# od-aws.net
KiCad netlist of a schematic drawn in EAGLE
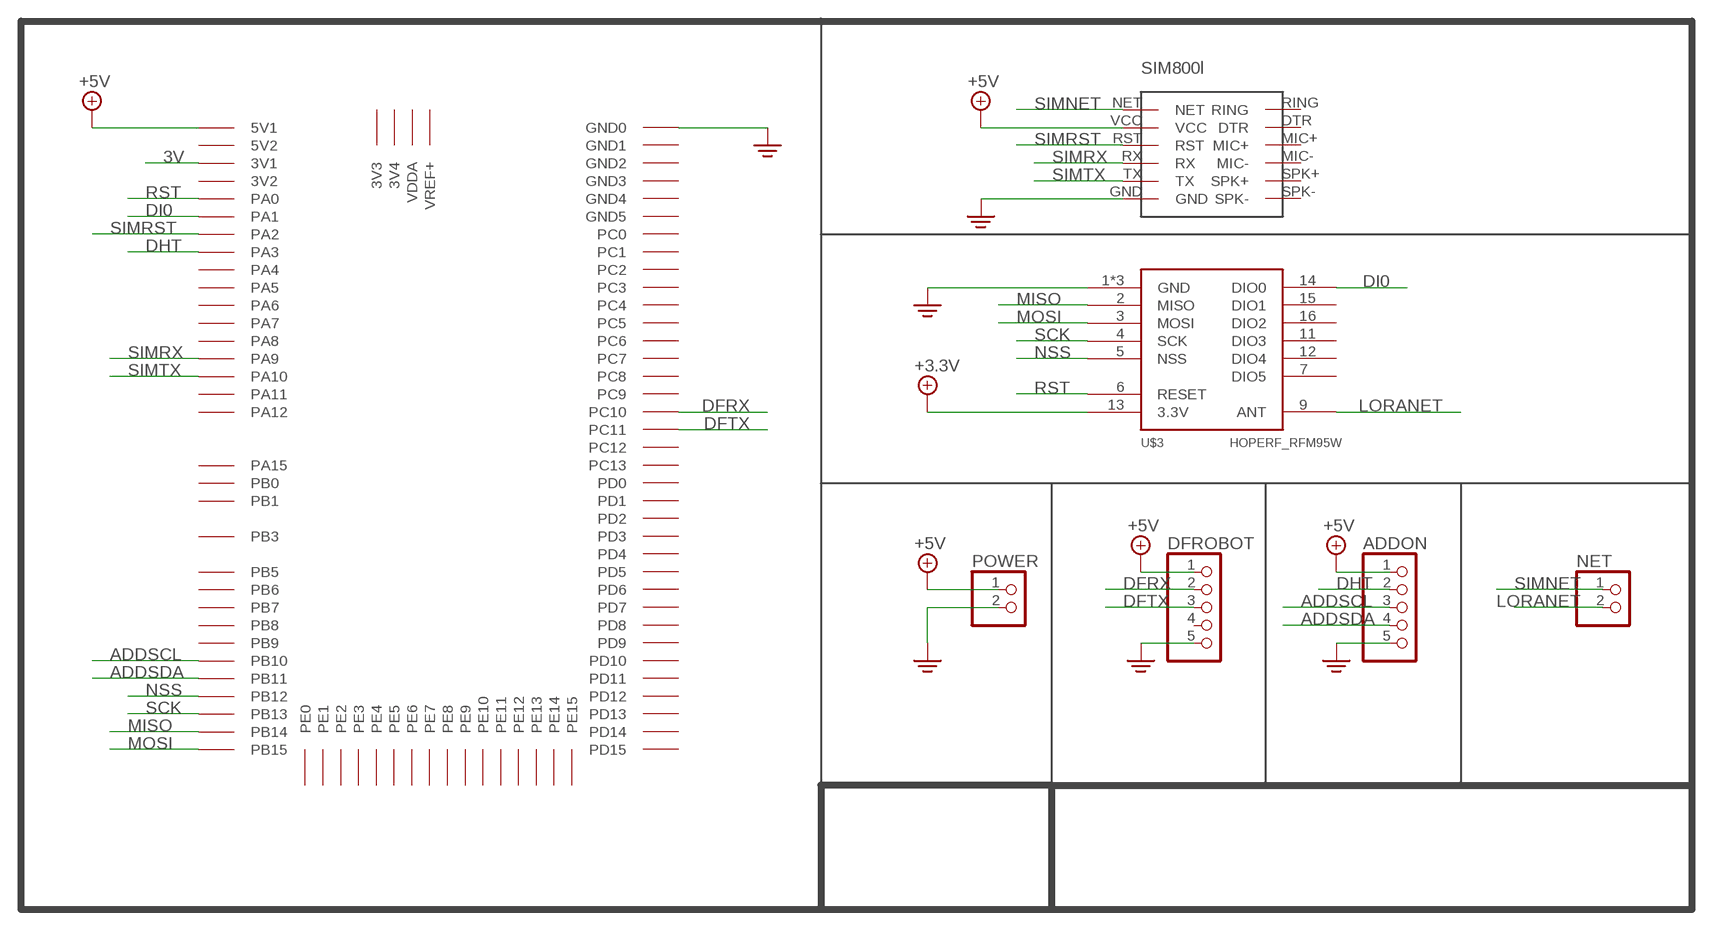
[diagram p0: schematic, sheet 1]

(export (version "E")
  (design (tool "Eeschema 10.0.6"))
  (components
    (comp (ref "ADDON")
      (value "PINHD-1X5/90")
      (footprint "eagle-import:1X05_90")
      (libsource (lib "eagle-import") (part "PINHD-1X5/90"))
    )
    (comp (ref "DFROBOT")
      (value "PINHD-1X5/90")
      (footprint "eagle-import:1X05_90")
      (libsource (lib "eagle-import") (part "PINHD-1X5/90"))
    )
    (comp (ref "NET")
      (value "PINHD-1X2/90")
      (footprint "eagle-import:1X02_90")
      (libsource (lib "eagle-import") (part "PINHD-1X2/90"))
    )
    (comp (ref "POWER")
      (value "PINHD-1X2/90")
      (footprint "eagle-import:1X02_90")
      (libsource (lib "eagle-import") (part "PINHD-1X2/90"))
    )
    (comp (ref "U$1")
      (value "STM32F407VGT6")
      (footprint "eagle-import:STM32F407VGT6")
      (libsource (lib "eagle-import") (part "STM32F407VGT6"))
    )
    (comp (ref "U$2")
      (value "SIM800L-V1")
      (footprint "eagle-import:SIM800L-V1")
      (libsource (lib "eagle-import") (part "SIM800L-V1"))
    )
    (comp (ref "U$3")
      (value "HOPERF_RFM95W")
      (footprint "eagle-import:HOPERF_RFM95W")
      (libsource (lib "eagle-import") (part "HOPERF_RFM95W"))
    )
  )
  (nets
    (net (code "1") (name "+3.3V") (class "Default")
      (node (ref "ADDON") (pin "1") (pinfunction "1_1") (pintype "passive"))
      (node (ref "DFROBOT") (pin "1") (pinfunction "1_1") (pintype "passive"))
      (node (ref "POWER") (pin "1") (pinfunction "1_1") (pintype "passive"))
      (node (ref "U$1") (pin "5V1") (pinfunction "5V1_5V1") (pintype "bidirectional"))
      (node (ref "U$2") (pin "VCC") (pinfunction "VCC_VCC") (pintype "bidirectional"))
      (node (ref "U$3") (pin "13") (pinfunction "3.3V_13") (pintype "power_in"))
    )
    (net (code "2") (name "/3V") (class "Default")
      (node (ref "U$1") (pin "3V31") (pinfunction "3V1_3V31") (pintype "bidirectional"))
    )
    (net (code "3") (name "/ADDSCL") (class "Default")
      (node (ref "ADDON") (pin "3") (pinfunction "3_3") (pintype "passive"))
      (node (ref "U$1") (pin "PB10") (pinfunction "PB10_PB10") (pintype "bidirectional"))
    )
    (net (code "4") (name "/ADDSDA") (class "Default")
      (node (ref "ADDON") (pin "4") (pinfunction "4_4") (pintype "passive"))
      (node (ref "U$1") (pin "PB11") (pinfunction "PB11_PB11") (pintype "bidirectional"))
    )
    (net (code "5") (name "/DFRX") (class "Default")
      (node (ref "DFROBOT") (pin "2") (pinfunction "2_2") (pintype "passive"))
      (node (ref "U$1") (pin "PC10") (pinfunction "PC10_PC10") (pintype "bidirectional"))
    )
    (net (code "6") (name "/DFTX") (class "Default")
      (node (ref "DFROBOT") (pin "3") (pinfunction "3_3") (pintype "passive"))
      (node (ref "U$1") (pin "PC11") (pinfunction "PC11_PC11") (pintype "bidirectional"))
    )
    (net (code "7") (name "/DHT") (class "Default")
      (node (ref "ADDON") (pin "2") (pinfunction "2_2") (pintype "passive"))
      (node (ref "U$1") (pin "PA3") (pinfunction "PA3_PA3") (pintype "bidirectional"))
    )
    (net (code "8") (name "/DI0") (class "Default")
      (node (ref "U$1") (pin "PA1") (pinfunction "PA1_PA1") (pintype "bidirectional"))
      (node (ref "U$3") (pin "14") (pinfunction "DIO0_14") (pintype "bidirectional"))
    )
    (net (code "9") (name "/LORANET") (class "Default")
      (node (ref "NET") (pin "2") (pinfunction "2_2") (pintype "passive"))
      (node (ref "U$3") (pin "9") (pinfunction "ANT_9") (pintype "bidirectional"))
    )
    (net (code "10") (name "/MISO") (class "Default")
      (node (ref "U$1") (pin "PB14") (pinfunction "PB14_PB14") (pintype "bidirectional"))
      (node (ref "U$3") (pin "2") (pinfunction "MISO_2") (pintype "input"))
    )
    (net (code "11") (name "/MOSI") (class "Default")
      (node (ref "U$1") (pin "PB15") (pinfunction "PB15_PB15") (pintype "bidirectional"))
      (node (ref "U$3") (pin "3") (pinfunction "MOSI_3") (pintype "output"))
    )
    (net (code "12") (name "/NSS") (class "Default")
      (node (ref "U$1") (pin "PB12") (pinfunction "PB12_PB12") (pintype "bidirectional"))
      (node (ref "U$3") (pin "5") (pinfunction "NSS_5") (pintype "input"))
    )
    (net (code "13") (name "/RST") (class "Default")
      (node (ref "U$1") (pin "PA0") (pinfunction "PA0_PA0") (pintype "bidirectional"))
      (node (ref "U$3") (pin "6") (pinfunction "RESET_6") (pintype "bidirectional"))
    )
    (net (code "14") (name "/SCK") (class "Default")
      (node (ref "U$1") (pin "PB13") (pinfunction "PB13_PB13") (pintype "bidirectional"))
      (node (ref "U$3") (pin "4") (pinfunction "SCK_4") (pintype "input"))
    )
    (net (code "15") (name "/SIMNET") (class "Default")
      (node (ref "NET") (pin "1") (pinfunction "1_1") (pintype "passive"))
      (node (ref "U$2") (pin "NET") (pinfunction "NET_NET") (pintype "bidirectional"))
    )
    (net (code "16") (name "/SIMRST") (class "Default")
      (node (ref "U$1") (pin "PA2") (pinfunction "PA2_PA2") (pintype "bidirectional"))
      (node (ref "U$2") (pin "RST") (pinfunction "RST_RST") (pintype "bidirectional"))
    )
    (net (code "17") (name "/SIMRX") (class "Default")
      (node (ref "U$1") (pin "PA9") (pinfunction "PA9_PA9") (pintype "bidirectional"))
      (node (ref "U$2") (pin "RX") (pinfunction "RX_RX") (pintype "bidirectional"))
    )
    (net (code "18") (name "/SIMTX") (class "Default")
      (node (ref "U$1") (pin "PA10") (pinfunction "PA10_PA10") (pintype "bidirectional"))
      (node (ref "U$2") (pin "TX") (pinfunction "TX_TX") (pintype "bidirectional"))
    )
    (net (code "19") (name "PE") (class "Default")
      (node (ref "ADDON") (pin "5") (pinfunction "5_5") (pintype "passive"))
      (node (ref "DFROBOT") (pin "5") (pinfunction "5_5") (pintype "passive"))
      (node (ref "POWER") (pin "2") (pinfunction "2_2") (pintype "passive"))
      (node (ref "U$1") (pin "GND1") (pinfunction "GND0_GND1") (pintype "bidirectional"))
      (node (ref "U$2") (pin "GND") (pinfunction "GND_GND") (pintype "bidirectional"))
      (node (ref "U$3") (pin "1") (pinfunction "GND_1") (pintype "power_in"))
      (node (ref "U$3") (pin "10") (pinfunction "GND_10") (pintype "power_in"))
      (node (ref "U$3") (pin "8") (pinfunction "GND_8") (pintype "power_in"))
    )
    (net (code "20") (name "unconnected-(DFROBOT-Pad4)") (class "Default")
      (node (ref "DFROBOT") (pin "4") (pinfunction "4_4") (pintype "passive"))
    )
    (net (code "21") (name "unconnected-(U$1-3V2-Pad3V32)") (class "Default")
      (node (ref "U$1") (pin "3V32") (pinfunction "3V2_3V32") (pintype "bidirectional"))
    )
    (net (code "22") (name "unconnected-(U$1-3V3-Pad3V33)") (class "Default")
      (node (ref "U$1") (pin "3V33") (pinfunction "3V3_3V33") (pintype "bidirectional"))
    )
    (net (code "23") (name "unconnected-(U$1-3V4-Pad3V34)") (class "Default")
      (node (ref "U$1") (pin "3V34") (pinfunction "3V4_3V34") (pintype "bidirectional"))
    )
    (net (code "24") (name "unconnected-(U$1-GND1-PadGND2)") (class "Default")
      (node (ref "U$1") (pin "GND2") (pinfunction "GND1_GND2") (pintype "bidirectional"))
    )
    (net (code "25") (name "unconnected-(U$1-GND2-PadGND3)") (class "Default")
      (node (ref "U$1") (pin "GND3") (pinfunction "GND2_GND3") (pintype "bidirectional"))
    )
    (net (code "26") (name "unconnected-(U$1-GND3-PadGND4)") (class "Default")
      (node (ref "U$1") (pin "GND4") (pinfunction "GND3_GND4") (pintype "bidirectional"))
    )
    (net (code "27") (name "unconnected-(U$1-GND4-PadGND5)") (class "Default")
      (node (ref "U$1") (pin "GND5") (pinfunction "GND4_GND5") (pintype "bidirectional"))
    )
    (net (code "28") (name "unconnected-(U$1-GND5-PadGND7)") (class "Default")
      (node (ref "U$1") (pin "GND7") (pinfunction "GND5_GND7") (pintype "bidirectional"))
    )
    (net (code "29") (name "unconnected-(U$1-Pad5V2)") (class "Default")
      (node (ref "U$1") (pin "5V2") (pinfunction "5V2_5V2") (pintype "bidirectional"))
    )
    (net (code "30") (name "unconnected-(U$1-PadPA4)") (class "Default")
      (node (ref "U$1") (pin "PA4") (pinfunction "PA4_PA4") (pintype "bidirectional"))
    )
    (net (code "31") (name "unconnected-(U$1-PadPA5)") (class "Default")
      (node (ref "U$1") (pin "PA5") (pinfunction "PA5_PA5") (pintype "bidirectional"))
    )
    (net (code "32") (name "unconnected-(U$1-PadPA6)") (class "Default")
      (node (ref "U$1") (pin "PA6") (pinfunction "PA6_PA6") (pintype "bidirectional"))
    )
    (net (code "33") (name "unconnected-(U$1-PadPA7)") (class "Default")
      (node (ref "U$1") (pin "PA7") (pinfunction "PA7_PA7") (pintype "bidirectional"))
    )
    (net (code "34") (name "unconnected-(U$1-PadPA8)") (class "Default")
      (node (ref "U$1") (pin "PA8") (pinfunction "PA8_PA8") (pintype "bidirectional"))
    )
    (net (code "35") (name "unconnected-(U$1-PadPA11)") (class "Default")
      (node (ref "U$1") (pin "PA11") (pinfunction "PA11_PA11") (pintype "bidirectional"))
    )
    (net (code "36") (name "unconnected-(U$1-PadPA12)") (class "Default")
      (node (ref "U$1") (pin "PA12") (pinfunction "PA12_PA12") (pintype "bidirectional"))
    )
    (net (code "37") (name "unconnected-(U$1-PadPA15)") (class "Default")
      (node (ref "U$1") (pin "PA15") (pinfunction "PA15_PA15") (pintype "bidirectional"))
    )
    (net (code "38") (name "unconnected-(U$1-PadPB0)") (class "Default")
      (node (ref "U$1") (pin "PB0") (pinfunction "PB0_PB0") (pintype "bidirectional"))
    )
    (net (code "39") (name "unconnected-(U$1-PadPB1)") (class "Default")
      (node (ref "U$1") (pin "PB1") (pinfunction "PB1_PB1") (pintype "bidirectional"))
    )
    (net (code "40") (name "unconnected-(U$1-PadPB3)") (class "Default")
      (node (ref "U$1") (pin "PB3") (pinfunction "PB3_PB3") (pintype "bidirectional"))
    )
    (net (code "41") (name "unconnected-(U$1-PadPB5)") (class "Default")
      (node (ref "U$1") (pin "PB5") (pinfunction "PB5_PB5") (pintype "bidirectional"))
    )
    (net (code "42") (name "unconnected-(U$1-PadPB6)") (class "Default")
      (node (ref "U$1") (pin "PB6") (pinfunction "PB6_PB6") (pintype "bidirectional"))
    )
    (net (code "43") (name "unconnected-(U$1-PadPB7)") (class "Default")
      (node (ref "U$1") (pin "PB7") (pinfunction "PB7_PB7") (pintype "bidirectional"))
    )
    (net (code "44") (name "unconnected-(U$1-PadPB8)") (class "Default")
      (node (ref "U$1") (pin "PB8") (pinfunction "PB8_PB8") (pintype "bidirectional"))
    )
    (net (code "45") (name "unconnected-(U$1-PadPB9)") (class "Default")
      (node (ref "U$1") (pin "PB9") (pinfunction "PB9_PB9") (pintype "bidirectional"))
    )
    (net (code "46") (name "unconnected-(U$1-PadPC0)") (class "Default")
      (node (ref "U$1") (pin "PC0") (pinfunction "PC0_PC0") (pintype "bidirectional"))
    )
    (net (code "47") (name "unconnected-(U$1-PadPC1)") (class "Default")
      (node (ref "U$1") (pin "PC1") (pinfunction "PC1_PC1") (pintype "bidirectional"))
    )
    (net (code "48") (name "unconnected-(U$1-PadPC2)") (class "Default")
      (node (ref "U$1") (pin "PC2") (pinfunction "PC2_PC2") (pintype "bidirectional"))
    )
    (net (code "49") (name "unconnected-(U$1-PadPC3)") (class "Default")
      (node (ref "U$1") (pin "PC3") (pinfunction "PC3_PC3") (pintype "bidirectional"))
    )
    (net (code "50") (name "unconnected-(U$1-PadPC4)") (class "Default")
      (node (ref "U$1") (pin "PC4") (pinfunction "PC4_PC4") (pintype "bidirectional"))
    )
    (net (code "51") (name "unconnected-(U$1-PadPC5)") (class "Default")
      (node (ref "U$1") (pin "PC5") (pinfunction "PC5_PC5") (pintype "bidirectional"))
    )
    (net (code "52") (name "unconnected-(U$1-PadPC6)") (class "Default")
      (node (ref "U$1") (pin "PC6") (pinfunction "PC6_PC6") (pintype "bidirectional"))
    )
    (net (code "53") (name "unconnected-(U$1-PadPC7)") (class "Default")
      (node (ref "U$1") (pin "PC7") (pinfunction "PC7_PC7") (pintype "bidirectional"))
    )
    (net (code "54") (name "unconnected-(U$1-PadPC8)") (class "Default")
      (node (ref "U$1") (pin "PC8") (pinfunction "PC8_PC8") (pintype "bidirectional"))
    )
    (net (code "55") (name "unconnected-(U$1-PadPC9)") (class "Default")
      (node (ref "U$1") (pin "PC9") (pinfunction "PC9_PC9") (pintype "bidirectional"))
    )
    (net (code "56") (name "unconnected-(U$1-PadPC12)") (class "Default")
      (node (ref "U$1") (pin "PC12") (pinfunction "PC12_PC12") (pintype "bidirectional"))
    )
    (net (code "57") (name "unconnected-(U$1-PadPC13)") (class "Default")
      (node (ref "U$1") (pin "PC13") (pinfunction "PC13_PC13") (pintype "bidirectional"))
    )
    (net (code "58") (name "unconnected-(U$1-PadPD0)") (class "Default")
      (node (ref "U$1") (pin "PD0") (pinfunction "PD0_PD0") (pintype "bidirectional"))
    )
    (net (code "59") (name "unconnected-(U$1-PadPD1)") (class "Default")
      (node (ref "U$1") (pin "PD1") (pinfunction "PD1_PD1") (pintype "bidirectional"))
    )
    (net (code "60") (name "unconnected-(U$1-PadPD2)") (class "Default")
      (node (ref "U$1") (pin "PD2") (pinfunction "PD2_PD2") (pintype "bidirectional"))
    )
    (net (code "61") (name "unconnected-(U$1-PadPD3)") (class "Default")
      (node (ref "U$1") (pin "PD3") (pinfunction "PD3_PD3") (pintype "bidirectional"))
    )
    (net (code "62") (name "unconnected-(U$1-PadPD4)") (class "Default")
      (node (ref "U$1") (pin "PD4") (pinfunction "PD4_PD4") (pintype "bidirectional"))
    )
    (net (code "63") (name "unconnected-(U$1-PadPD5)") (class "Default")
      (node (ref "U$1") (pin "PD5") (pinfunction "PD5_PD5") (pintype "bidirectional"))
    )
    (net (code "64") (name "unconnected-(U$1-PadPD6)") (class "Default")
      (node (ref "U$1") (pin "PD6") (pinfunction "PD6_PD6") (pintype "bidirectional"))
    )
    (net (code "65") (name "unconnected-(U$1-PadPD7)") (class "Default")
      (node (ref "U$1") (pin "PD7") (pinfunction "PD7_PD7") (pintype "bidirectional"))
    )
    (net (code "66") (name "unconnected-(U$1-PadPD8)") (class "Default")
      (node (ref "U$1") (pin "PD8") (pinfunction "PD8_PD8") (pintype "bidirectional"))
    )
    (net (code "67") (name "unconnected-(U$1-PadPD9)") (class "Default")
      (node (ref "U$1") (pin "PD9") (pinfunction "PD9_PD9") (pintype "bidirectional"))
    )
    (net (code "68") (name "unconnected-(U$1-PadPD10)") (class "Default")
      (node (ref "U$1") (pin "PD10") (pinfunction "PD10_PD10") (pintype "bidirectional"))
    )
    (net (code "69") (name "unconnected-(U$1-PadPD11)") (class "Default")
      (node (ref "U$1") (pin "PD11") (pinfunction "PD11_PD11") (pintype "bidirectional"))
    )
    (net (code "70") (name "unconnected-(U$1-PadPD12)") (class "Default")
      (node (ref "U$1") (pin "PD12") (pinfunction "PD12_PD12") (pintype "bidirectional"))
    )
    (net (code "71") (name "unconnected-(U$1-PadPD13)") (class "Default")
      (node (ref "U$1") (pin "PD13") (pinfunction "PD13_PD13") (pintype "bidirectional"))
    )
    (net (code "72") (name "unconnected-(U$1-PadPD14)") (class "Default")
      (node (ref "U$1") (pin "PD14") (pinfunction "PD14_PD14") (pintype "bidirectional"))
    )
    (net (code "73") (name "unconnected-(U$1-PadPD15)") (class "Default")
      (node (ref "U$1") (pin "PD15") (pinfunction "PD15_PD15") (pintype "bidirectional"))
    )
    (net (code "74") (name "unconnected-(U$1-PadPE0)") (class "Default")
      (node (ref "U$1") (pin "PE0") (pinfunction "PE0_PE0") (pintype "bidirectional"))
    )
    (net (code "75") (name "unconnected-(U$1-PadPE1)") (class "Default")
      (node (ref "U$1") (pin "PE1") (pinfunction "PE1_PE1") (pintype "bidirectional"))
    )
    (net (code "76") (name "unconnected-(U$1-PadPE2)") (class "Default")
      (node (ref "U$1") (pin "PE2") (pinfunction "PE2_PE2") (pintype "bidirectional"))
    )
    (net (code "77") (name "unconnected-(U$1-PadPE3)") (class "Default")
      (node (ref "U$1") (pin "PE3") (pinfunction "PE3_PE3") (pintype "bidirectional"))
    )
    (net (code "78") (name "unconnected-(U$1-PadPE4)") (class "Default")
      (node (ref "U$1") (pin "PE4") (pinfunction "PE4_PE4") (pintype "bidirectional"))
    )
    (net (code "79") (name "unconnected-(U$1-PadPE5)") (class "Default")
      (node (ref "U$1") (pin "PE5") (pinfunction "PE5_PE5") (pintype "bidirectional"))
    )
    (net (code "80") (name "unconnected-(U$1-PadPE6)") (class "Default")
      (node (ref "U$1") (pin "PE6") (pinfunction "PE6_PE6") (pintype "bidirectional"))
    )
    (net (code "81") (name "unconnected-(U$1-PadPE7)") (class "Default")
      (node (ref "U$1") (pin "PE7") (pinfunction "PE7_PE7") (pintype "bidirectional"))
    )
    (net (code "82") (name "unconnected-(U$1-PadPE8)") (class "Default")
      (node (ref "U$1") (pin "PE8") (pinfunction "PE8_PE8") (pintype "bidirectional"))
    )
    (net (code "83") (name "unconnected-(U$1-PadPE9)") (class "Default")
      (node (ref "U$1") (pin "PE9") (pinfunction "PE9_PE9") (pintype "bidirectional"))
    )
    (net (code "84") (name "unconnected-(U$1-PadPE10)") (class "Default")
      (node (ref "U$1") (pin "PE10") (pinfunction "PE10_PE10") (pintype "bidirectional"))
    )
    (net (code "85") (name "unconnected-(U$1-PadPE11)") (class "Default")
      (node (ref "U$1") (pin "PE11") (pinfunction "PE11_PE11") (pintype "bidirectional"))
    )
    (net (code "86") (name "unconnected-(U$1-PadPE12)") (class "Default")
      (node (ref "U$1") (pin "PE12") (pinfunction "PE12_PE12") (pintype "bidirectional"))
    )
    (net (code "87") (name "unconnected-(U$1-PadPE13)") (class "Default")
      (node (ref "U$1") (pin "PE13") (pinfunction "PE13_PE13") (pintype "bidirectional"))
    )
    (net (code "88") (name "unconnected-(U$1-PadPE14)") (class "Default")
      (node (ref "U$1") (pin "PE14") (pinfunction "PE14_PE14") (pintype "bidirectional"))
    )
    (net (code "89") (name "unconnected-(U$1-PadPE15)") (class "Default")
      (node (ref "U$1") (pin "PE15") (pinfunction "PE15_PE15") (pintype "bidirectional"))
    )
    (net (code "90") (name "unconnected-(U$1-PadVDDA)") (class "Default")
      (node (ref "U$1") (pin "VDDA") (pinfunction "VDDA_VDDA") (pintype "bidirectional"))
    )
    (net (code "91") (name "unconnected-(U$1-PadVREF+)") (class "Default")
      (node (ref "U$1") (pin "VREF+") (pinfunction "VREF+_VREF+") (pintype "bidirectional"))
    )
    (net (code "92") (name "unconnected-(U$2-PadDTR)") (class "Default")
      (node (ref "U$2") (pin "DTR") (pinfunction "DTR_DTR") (pintype "bidirectional"))
    )
    (net (code "93") (name "unconnected-(U$2-PadMIC+)") (class "Default")
      (node (ref "U$2") (pin "MIC+") (pinfunction "MIC+_MIC+") (pintype "bidirectional"))
    )
    (net (code "94") (name "unconnected-(U$2-PadMIC-)") (class "Default")
      (node (ref "U$2") (pin "MIC-") (pinfunction "MIC-_MIC-") (pintype "bidirectional"))
    )
    (net (code "95") (name "unconnected-(U$2-PadRING)") (class "Default")
      (node (ref "U$2") (pin "RING") (pinfunction "RING_RING") (pintype "bidirectional"))
    )
    (net (code "96") (name "unconnected-(U$2-PadSPK+)") (class "Default")
      (node (ref "U$2") (pin "SPK+") (pinfunction "SPK+_SPK+") (pintype "bidirectional"))
    )
    (net (code "97") (name "unconnected-(U$2-PadSPK-)") (class "Default")
      (node (ref "U$2") (pin "SPK-") (pinfunction "SPK-_SPK-") (pintype "bidirectional"))
    )
    (net (code "98") (name "unconnected-(U$3-DIO1-Pad15)") (class "Default")
      (node (ref "U$3") (pin "15") (pinfunction "DIO1_15") (pintype "bidirectional"))
    )
    (net (code "99") (name "unconnected-(U$3-DIO2-Pad16)") (class "Default")
      (node (ref "U$3") (pin "16") (pinfunction "DIO2_16") (pintype "bidirectional"))
    )
    (net (code "100") (name "unconnected-(U$3-DIO3-Pad11)") (class "Default")
      (node (ref "U$3") (pin "11") (pinfunction "DIO3_11") (pintype "bidirectional"))
    )
    (net (code "101") (name "unconnected-(U$3-DIO4-Pad12)") (class "Default")
      (node (ref "U$3") (pin "12") (pinfunction "DIO4_12") (pintype "bidirectional"))
    )
    (net (code "102") (name "unconnected-(U$3-DIO5-Pad7)") (class "Default")
      (node (ref "U$3") (pin "7") (pinfunction "DIO5_7") (pintype "bidirectional"))
    )
  )
)
